# watch.net
KiCad netlist of a schematic drawn in EAGLE
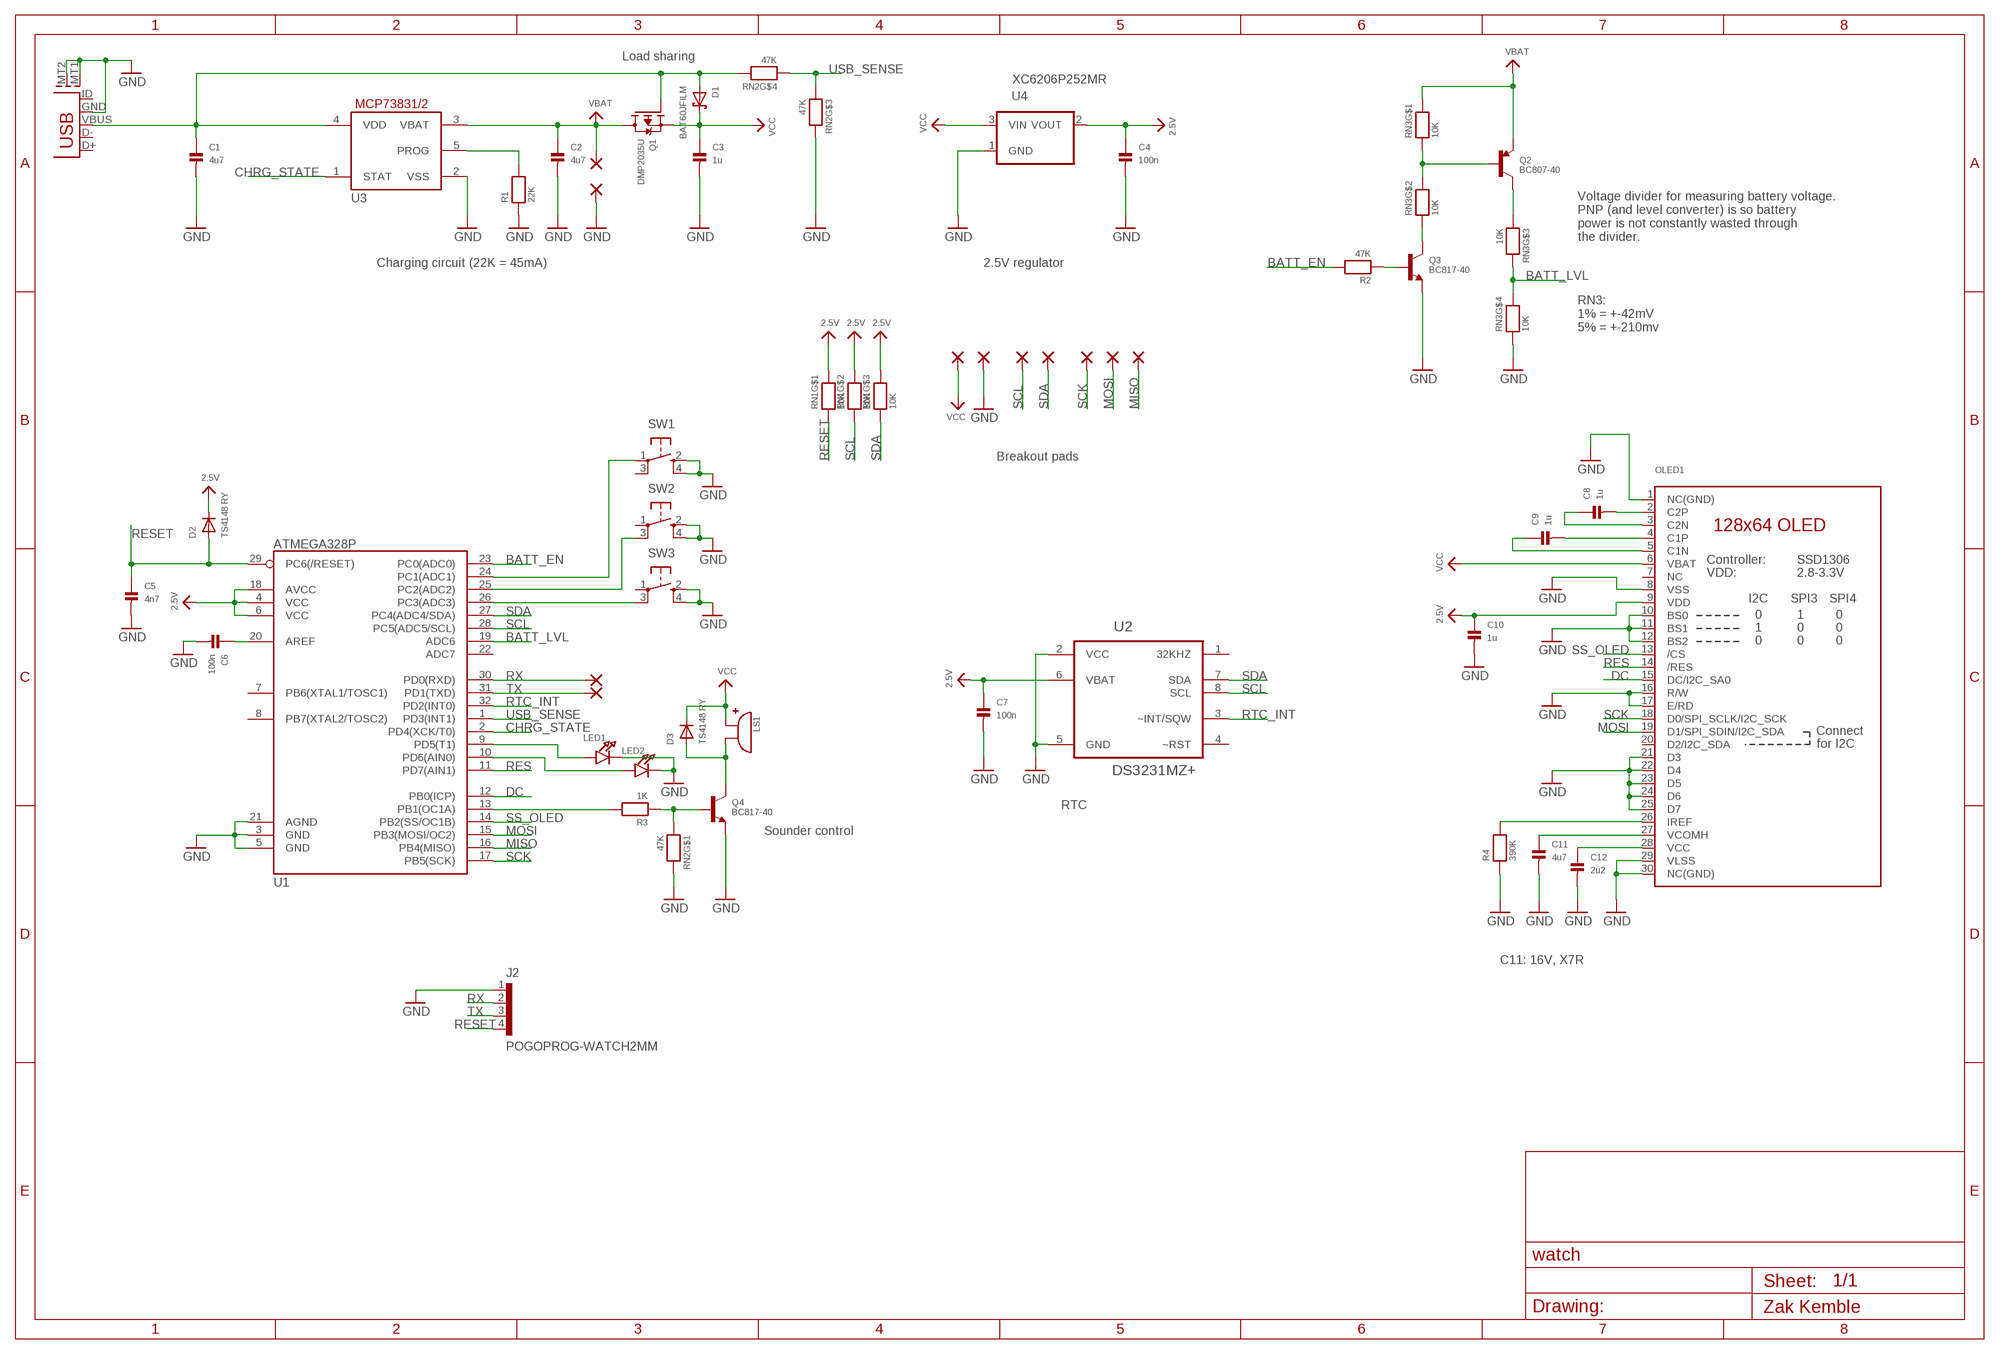
[diagram p0: schematic, sheet 1]

(export (version "E")
  (design (tool "Eeschema 10.0.6"))
  (components
    (comp (ref "C1")
      (value "4u7")
      (footprint "eagle-import:0805")
      (libsource (lib "eagle-import") (part "CAP_CERAMIC0805"))
    )
    (comp (ref "C2")
      (value "4u7")
      (footprint "eagle-import:0805")
      (libsource (lib "eagle-import") (part "CAP_CERAMIC0805"))
    )
    (comp (ref "C3")
      (value "1u")
      (footprint "eagle-import:0805")
      (libsource (lib "eagle-import") (part "CAP_CERAMIC0805"))
    )
    (comp (ref "C4")
      (value "100n")
      (footprint "eagle-import:0805")
      (libsource (lib "eagle-import") (part "CAP_CERAMIC0805"))
    )
    (comp (ref "C5")
      (value "4n7")
      (footprint "eagle-import:0805")
      (libsource (lib "eagle-import") (part "CAP_CERAMIC0805"))
    )
    (comp (ref "C6")
      (value "100n")
      (footprint "eagle-import:0805")
      (libsource (lib "eagle-import") (part "CAP_CERAMIC0805"))
    )
    (comp (ref "C7")
      (value "100n")
      (footprint "eagle-import:0805")
      (libsource (lib "eagle-import") (part "CAP_CERAMIC0805"))
    )
    (comp (ref "C8")
      (value "1u")
      (footprint "eagle-import:0805")
      (libsource (lib "eagle-import") (part "CAP_CERAMIC0805"))
    )
    (comp (ref "C9")
      (value "1u")
      (footprint "eagle-import:0805")
      (libsource (lib "eagle-import") (part "CAP_CERAMIC0805"))
    )
    (comp (ref "C10")
      (value "1u")
      (footprint "eagle-import:0805")
      (libsource (lib "eagle-import") (part "CAP_CERAMIC0805"))
    )
    (comp (ref "C11")
      (value "4u7")
      (footprint "eagle-import:0805")
      (libsource (lib "eagle-import") (part "CAP_CERAMIC0805"))
    )
    (comp (ref "C12")
      (value "2u2")
      (footprint "eagle-import:0805")
      (libsource (lib "eagle-import") (part "CAP_CERAMIC0805"))
    )
    (comp (ref "D1")
      (value "BAT60JFILM")
      (footprint "eagle-import:SOD-323")
      (libsource (lib "eagle-import") (part "DIODE-SCHOTTKYSOD-323"))
    )
    (comp (ref "D2")
      (value "TS4148 RY")
      (footprint "eagle-import:0805_DIODE")
      (libsource (lib "eagle-import") (part "DIODE_08050805"))
    )
    (comp (ref "D3")
      (value "TS4148 RY")
      (footprint "eagle-import:0805_DIODE")
      (libsource (lib "eagle-import") (part "DIODE_08050805"))
    )
    (comp (ref "J2")
      (value "POGOPROG-WATCH2MM")
      (footprint "eagle-import:POGOPROG_WATCH_2MM")
      (libsource (lib "eagle-import") (part "POGOPROG-WATCH2MM"))
    )
    (comp (ref "LED1")
      (value "LED0805")
      (footprint "eagle-import:CHIPLED_0805")
      (libsource (lib "eagle-import") (part "LED0805"))
    )
    (comp (ref "LED2")
      (value "LED0805")
      (footprint "eagle-import:CHIPLED_0805")
      (libsource (lib "eagle-import") (part "LED0805"))
    )
    (comp (ref "LS1")
      (value "ABMT-801-RC")
      (footprint "eagle-import:PIEZO")
      (libsource (lib "eagle-import") (part "ABMT-801-RC"))
    )
    (comp (ref "OLED1")
      (value "DISP_OLED_UG-2864HSWEG01_NOOUTLINEWATCH")
      (footprint "eagle-import:UG-2864HSWEG01_1.3_WRAPAROUND_WATCH")
      (libsource (lib "eagle-import") (part "DISP_OLED_UG-2864HSWEG01_NOOUTLINEWATCH"))
    )
    (comp (ref "PAD1")
      (value "SMD2")
      (footprint "eagle-import:SMD1,27-2,54")
      (libsource (lib "eagle-import") (part "SMD2"))
    )
    (comp (ref "PAD2")
      (value "SMD2")
      (footprint "eagle-import:SMD1,27-2,54")
      (libsource (lib "eagle-import") (part "SMD2"))
    )
    (comp (ref "PAD3")
      (value "SMD2")
      (footprint "eagle-import:SMD1,27-2,54")
      (libsource (lib "eagle-import") (part "SMD2"))
    )
    (comp (ref "PAD4")
      (value "SMD2")
      (footprint "eagle-import:SMD1,27-2,54")
      (libsource (lib "eagle-import") (part "SMD2"))
    )
    (comp (ref "PAD5")
      (value "SMD2")
      (footprint "eagle-import:SMD1,27-2,54")
      (libsource (lib "eagle-import") (part "SMD2"))
    )
    (comp (ref "PAD6")
      (value "SMD2")
      (footprint "eagle-import:SMD1,27-2,54")
      (libsource (lib "eagle-import") (part "SMD2"))
    )
    (comp (ref "PAD7")
      (value "SMD2")
      (footprint "eagle-import:SMD1,27-2,54")
      (libsource (lib "eagle-import") (part "SMD2"))
    )
    (comp (ref "PAD8")
      (value "SMD2")
      (footprint "eagle-import:SMD1,27-2,54")
      (libsource (lib "eagle-import") (part "SMD2"))
    )
    (comp (ref "PAD10")
      (value "SMD2")
      (footprint "eagle-import:SMD1,27-2,54")
      (libsource (lib "eagle-import") (part "SMD2"))
    )
    (comp (ref "PAD11")
      (value "SMD2")
      (footprint "eagle-import:SMD1,27-2,54")
      (libsource (lib "eagle-import") (part "SMD2"))
    )
    (comp (ref "PAD12")
      (value "SMD2")
      (footprint "eagle-import:SMD1,27-2,54")
      (libsource (lib "eagle-import") (part "SMD2"))
    )
    (comp (ref "Q1")
      (value "DMP2035U")
      (footprint "eagle-import:SOT23-WIDE")
      (libsource (lib "eagle-import") (part "MOSFET-PWIDE"))
    )
    (comp (ref "Q2")
      (value "BC807-40")
      (footprint "eagle-import:SOT23-WIDE")
      (libsource (lib "eagle-import") (part "TRANSISTOR_PNPWIDE"))
    )
    (comp (ref "Q3")
      (value "BC817-40")
      (footprint "eagle-import:SOT23-WIDE")
      (libsource (lib "eagle-import") (part "TRANSISTOR_NPNWIDE"))
    )
    (comp (ref "Q4")
      (value "BC817-40")
      (footprint "eagle-import:SOT23-WIDE")
      (libsource (lib "eagle-import") (part "TRANSISTOR_NPNWIDE"))
    )
    (comp (ref "R1")
      (value "22K")
      (footprint "eagle-import:0805")
      (libsource (lib "eagle-import") (part "RESISTOR0805"))
    )
    (comp (ref "R2")
      (value "47K")
      (footprint "eagle-import:0805")
      (libsource (lib "eagle-import") (part "RESISTOR0805"))
    )
    (comp (ref "R3")
      (value "1K")
      (footprint "eagle-import:0805")
      (libsource (lib "eagle-import") (part "RESISTOR0805"))
    )
    (comp (ref "R4")
      (value "390K")
      (footprint "eagle-import:0805")
      (libsource (lib "eagle-import") (part "RESISTOR0805"))
    )
    (comp (ref "RN1")
      (value "10K")
      (footprint "eagle-import:RESPACK_4X0603")
      (libsource (lib "eagle-import") (part "RESISTOR_4PACK"))
    )
    (comp (ref "RN2")
      (value "47K")
      (footprint "eagle-import:RESPACK_4X0603")
      (libsource (lib "eagle-import") (part "RESISTOR_4PACK"))
    )
    (comp (ref "RN3")
      (value "10K")
      (footprint "eagle-import:RESPACK_4X0603")
      (libsource (lib "eagle-import") (part "RESISTOR_4PACK"))
    )
    (comp (ref "SW1")
      (value "SPST_TACTRA")
      (footprint "eagle-import:TACT_SMD2")
      (libsource (lib "eagle-import") (part "SPST_TACTRA"))
    )
    (comp (ref "SW2")
      (value "SPST_TACTRA")
      (footprint "eagle-import:TACT_SMD2")
      (libsource (lib "eagle-import") (part "SPST_TACTRA"))
    )
    (comp (ref "SW3")
      (value "SPST_TACTRA")
      (footprint "eagle-import:TACT_SMD2")
      (libsource (lib "eagle-import") (part "SPST_TACTRA"))
    )
    (comp (ref "U1")
      (value "ATMEGA328P")
      (footprint "eagle-import:TQFP32-08")
      (libsource (lib "eagle-import") (part "ATMEGA328_SMT"))
    )
    (comp (ref "U2")
      (value "DS3231MZ+")
      (footprint "eagle-import:SOIC8_150MIL_SMPAD")
      (libsource (lib "eagle-import") (part "DS3231MZ+SMPAD"))
    )
    (comp (ref "U3")
      (value "MCP73832T-2ACI/OT")
      (footprint "eagle-import:SOT23-5L")
      (libsource (lib "eagle-import") (part "MCP73831/OT"))
    )
    (comp (ref "U4")
      (value "XC6206P252MR")
      (footprint "eagle-import:SOT-23")
      (libsource (lib "eagle-import") (part "MCP1700T-2502E/TTWIDE_PAD"))
    )
    (comp (ref "USB1")
      (value "USB-MICROBLARGEPAD")
      (footprint "eagle-import:USB-MICROB_LARGEPAD")
      (libsource (lib "eagle-import") (part "USB-MICROBLARGEPAD"))
    )
  )
  (nets
    (net (code "1") (name "/BATT_EN") (class "Default")
      (node (ref "R2") (pin "2") (pinfunction "2_2") (pintype "passive"))
      (node (ref "U1") (pin "23") (pinfunction "PC0(ADC0)_23") (pintype "bidirectional"))
    )
    (net (code "2") (name "/BATT_LVL") (class "Default")
      (node (ref "RN3") (pin "5") (pinfunction "2_5") (pintype "passive"))
      (node (ref "RN3") (pin "6") (pinfunction "2_6") (pintype "passive"))
      (node (ref "U1") (pin "19") (pinfunction "ADC6_19") (pintype "bidirectional"))
    )
    (net (code "3") (name "/CHRG_STATE") (class "Default")
      (node (ref "U1") (pin "2") (pinfunction "PD4(XCK/T0)_2") (pintype "bidirectional"))
      (node (ref "U3") (pin "1") (pinfunction "STAT_1") (pintype "output"))
    )
    (net (code "4") (name "/DC") (class "Default")
      (node (ref "OLED1") (pin "15") (pinfunction "DC/I2C_SA0_15") (pintype "input"))
      (node (ref "U1") (pin "12") (pinfunction "PB0(ICP)_12") (pintype "bidirectional"))
    )
    (net (code "5") (name "/MISO") (class "Default")
      (node (ref "PAD12") (pin "1") (pinfunction "P_1") (pintype "passive"))
      (node (ref "U1") (pin "16") (pinfunction "PB4(MISO)_16") (pintype "bidirectional"))
    )
    (net (code "6") (name "/MOSI") (class "Default")
      (node (ref "OLED1") (pin "19") (pinfunction "D1/SPI_SDIN/I2C_SDA_19") (pintype "bidirectional"))
      (node (ref "PAD11") (pin "1") (pinfunction "P_1") (pintype "passive"))
      (node (ref "U1") (pin "15") (pinfunction "PB3(MOSI/OC2)_15") (pintype "bidirectional"))
    )
    (net (code "7") (name "/RES") (class "Default")
      (node (ref "OLED1") (pin "14") (pinfunction "/RES_14") (pintype "input"))
      (node (ref "U1") (pin "11") (pinfunction "PD7(AIN1)_11") (pintype "bidirectional"))
    )
    (net (code "8") (name "/RESET") (class "Default")
      (node (ref "C5") (pin "1") (pinfunction "P$1_1") (pintype "passive"))
      (node (ref "D2") (pin "1") (pinfunction "A_1") (pintype "passive"))
      (node (ref "J2") (pin "4") (pinfunction "4_4") (pintype "bidirectional"))
      (node (ref "RN1") (pin "1") (pinfunction "1_1") (pintype "passive"))
      (node (ref "U1") (pin "29") (pinfunction "PC6(/RESET)_29") (pintype "bidirectional"))
    )
    (net (code "9") (name "/RTC_INT") (class "Default")
      (node (ref "U1") (pin "32") (pinfunction "PD2(INT0)_32") (pintype "bidirectional"))
      (node (ref "U2") (pin "3") (pinfunction "~{INT/SQW}_3") (pintype "output"))
    )
    (net (code "10") (name "/RX") (class "Default")
      (node (ref "J2") (pin "2") (pinfunction "2_2") (pintype "bidirectional"))
      (node (ref "PAD3") (pin "1") (pinfunction "P_1") (pintype "passive"))
      (node (ref "U1") (pin "30") (pinfunction "PD0(RXD)_30") (pintype "bidirectional"))
    )
    (net (code "11") (name "/SCK") (class "Default")
      (node (ref "OLED1") (pin "18") (pinfunction "D0/SPI_SCLK/I2C_SCK_18") (pintype "bidirectional"))
      (node (ref "PAD10") (pin "1") (pinfunction "P_1") (pintype "passive"))
      (node (ref "U1") (pin "17") (pinfunction "PB5(SCK)_17") (pintype "bidirectional"))
    )
    (net (code "12") (name "/SCL") (class "Default")
      (node (ref "PAD8") (pin "1") (pinfunction "P_1") (pintype "passive"))
      (node (ref "RN1") (pin "2") (pinfunction "1_2") (pintype "passive"))
      (node (ref "U1") (pin "28") (pinfunction "PC5(ADC5/SCL)_28") (pintype "bidirectional"))
      (node (ref "U2") (pin "8") (pinfunction "SCL_8") (pintype "input"))
    )
    (net (code "13") (name "/SDA") (class "Default")
      (node (ref "PAD7") (pin "1") (pinfunction "P_1") (pintype "passive"))
      (node (ref "RN1") (pin "3") (pinfunction "1_3") (pintype "passive"))
      (node (ref "U1") (pin "27") (pinfunction "PC4(ADC4/SDA)_27") (pintype "bidirectional"))
      (node (ref "U2") (pin "7") (pinfunction "SDA_7") (pintype "bidirectional"))
    )
    (net (code "14") (name "/SS_OLED") (class "Default")
      (node (ref "OLED1") (pin "13") (pinfunction "/CS_13") (pintype "input"))
      (node (ref "U1") (pin "14") (pinfunction "PB2(SS/OC1B)_14") (pintype "bidirectional"))
    )
    (net (code "15") (name "/TX") (class "Default")
      (node (ref "J2") (pin "3") (pinfunction "3_3") (pintype "bidirectional"))
      (node (ref "PAD4") (pin "1") (pinfunction "P_1") (pintype "passive"))
      (node (ref "U1") (pin "31") (pinfunction "PD1(TXD)_31") (pintype "bidirectional"))
    )
    (net (code "16") (name "/USB_SENSE") (class "Default")
      (node (ref "RN2") (pin "3") (pinfunction "1_3") (pintype "passive"))
      (node (ref "RN2") (pin "4") (pinfunction "1_4") (pintype "passive"))
      (node (ref "U1") (pin "1") (pinfunction "PD3(INT1)_1") (pintype "bidirectional"))
    )
    (net (code "17") (name "2.5V") (class "Default")
      (node (ref "C10") (pin "1") (pinfunction "P$1_1") (pintype "passive"))
      (node (ref "C4") (pin "1") (pinfunction "P$1_1") (pintype "passive"))
      (node (ref "C7") (pin "1") (pinfunction "P$1_1") (pintype "passive"))
      (node (ref "D2") (pin "2") (pinfunction "C_2") (pintype "passive"))
      (node (ref "OLED1") (pin "9") (pinfunction "VDD_9") (pintype "power_in"))
      (node (ref "RN1") (pin "6") (pinfunction "2_6") (pintype "passive"))
      (node (ref "RN1") (pin "7") (pinfunction "2_7") (pintype "passive"))
      (node (ref "RN1") (pin "8") (pinfunction "2_8") (pintype "passive"))
      (node (ref "U1") (pin "18") (pinfunction "AVCC_18") (pintype "bidirectional"))
      (node (ref "U1") (pin "4") (pinfunction "VCC_4") (pintype "bidirectional"))
      (node (ref "U1") (pin "6") (pinfunction "VCC_6") (pintype "bidirectional"))
      (node (ref "U2") (pin "6") (pinfunction "VBAT_6") (pintype "power_in"))
      (node (ref "U4") (pin "2") (pinfunction "VOUT_2") (pintype "output"))
    )
    (net (code "18") (name "GND") (class "Default")
      (node (ref "C1") (pin "2") (pinfunction "P$2_2") (pintype "passive"))
      (node (ref "C10") (pin "2") (pinfunction "P$2_2") (pintype "passive"))
      (node (ref "C11") (pin "2") (pinfunction "P$2_2") (pintype "passive"))
      (node (ref "C12") (pin "2") (pinfunction "P$2_2") (pintype "passive"))
      (node (ref "C2") (pin "2") (pinfunction "P$2_2") (pintype "passive"))
      (node (ref "C3") (pin "2") (pinfunction "P$2_2") (pintype "passive"))
      (node (ref "C4") (pin "2") (pinfunction "P$2_2") (pintype "passive"))
      (node (ref "C5") (pin "2") (pinfunction "P$2_2") (pintype "passive"))
      (node (ref "C6") (pin "2") (pinfunction "P$2_2") (pintype "passive"))
      (node (ref "C7") (pin "2") (pinfunction "P$2_2") (pintype "passive"))
      (node (ref "J2") (pin "1") (pinfunction "1_1") (pintype "bidirectional"))
      (node (ref "LED1") (pin "C") (pinfunction "C_C") (pintype "passive"))
      (node (ref "LED2") (pin "C") (pinfunction "C_C") (pintype "passive"))
      (node (ref "OLED1") (pin "1") (pinfunction "NC(GND)_1") (pintype "input"))
      (node (ref "OLED1") (pin "10") (pinfunction "BS0_10") (pintype "input"))
      (node (ref "OLED1") (pin "11") (pinfunction "BS1_11") (pintype "input"))
      (node (ref "OLED1") (pin "12") (pinfunction "BS2_12") (pintype "input"))
      (node (ref "OLED1") (pin "16") (pinfunction "R/W_16") (pintype "input"))
      (node (ref "OLED1") (pin "17") (pinfunction "E/RD_17") (pintype "input"))
      (node (ref "OLED1") (pin "21") (pinfunction "D3_21") (pintype "bidirectional"))
      (node (ref "OLED1") (pin "22") (pinfunction "D4_22") (pintype "bidirectional"))
      (node (ref "OLED1") (pin "23") (pinfunction "D5_23") (pintype "bidirectional"))
      (node (ref "OLED1") (pin "24") (pinfunction "D6_24") (pintype "bidirectional"))
      (node (ref "OLED1") (pin "25") (pinfunction "D7_25") (pintype "bidirectional"))
      (node (ref "OLED1") (pin "29") (pinfunction "VLSS_29") (pintype "power_in"))
      (node (ref "OLED1") (pin "30") (pinfunction "NC(GND)_30") (pintype "input"))
      (node (ref "OLED1") (pin "8") (pinfunction "VSS_8") (pintype "power_in"))
      (node (ref "PAD2") (pin "1") (pinfunction "P_1") (pintype "passive"))
      (node (ref "PAD5") (pin "1") (pinfunction "P_1") (pintype "passive"))
      (node (ref "Q3") (pin "2") (pinfunction "E_2") (pintype "passive"))
      (node (ref "Q4") (pin "2") (pinfunction "E_2") (pintype "passive"))
      (node (ref "R1") (pin "1") (pinfunction "1_1") (pintype "passive"))
      (node (ref "R4") (pin "1") (pinfunction "1_1") (pintype "passive"))
      (node (ref "RN2") (pin "6") (pinfunction "2_6") (pintype "passive"))
      (node (ref "RN2") (pin "8") (pinfunction "2_8") (pintype "passive"))
      (node (ref "RN3") (pin "4") (pinfunction "1_4") (pintype "passive"))
      (node (ref "SW1") (pin "2") (pinfunction "S_2") (pintype "passive"))
      (node (ref "SW1") (pin "4") (pinfunction "S1_4") (pintype "passive"))
      (node (ref "SW2") (pin "2") (pinfunction "S_2") (pintype "passive"))
      (node (ref "SW2") (pin "4") (pinfunction "S1_4") (pintype "passive"))
      (node (ref "SW3") (pin "2") (pinfunction "S_2") (pintype "passive"))
      (node (ref "SW3") (pin "4") (pinfunction "S1_4") (pintype "passive"))
      (node (ref "U1") (pin "21") (pinfunction "AGND_21") (pintype "bidirectional"))
      (node (ref "U1") (pin "3") (pinfunction "GND_3") (pintype "bidirectional"))
      (node (ref "U1") (pin "5") (pinfunction "GND_5") (pintype "bidirectional"))
      (node (ref "U2") (pin "2") (pinfunction "VCC_2") (pintype "power_in"))
      (node (ref "U2") (pin "5") (pinfunction "GND_5") (pintype "passive"))
      (node (ref "U3") (pin "2") (pinfunction "VSS_2") (pintype "power_in"))
      (node (ref "U4") (pin "1") (pinfunction "GND_1") (pintype "passive"))
      (node (ref "USB1") (pin "GND") (pinfunction "GND_GND") (pintype "bidirectional"))
      (node (ref "USB1") (pin "MT1") (pinfunction "SHEILD1_MT1") (pintype "bidirectional"))
      (node (ref "USB1") (pin "MT2") (pinfunction "SHEILD2_MT2") (pintype "bidirectional"))
    )
    (net (code "19") (name "Net-(C1-P$1)") (class "Default")
      (node (ref "C1") (pin "1") (pinfunction "P$1_1") (pintype "passive"))
      (node (ref "D1") (pin "A") (pinfunction "A_A") (pintype "passive"))
      (node (ref "Q1") (pin "1") (pinfunction "G_1") (pintype "passive"))
      (node (ref "RN2") (pin "5") (pinfunction "2_5") (pintype "passive"))
      (node (ref "U3") (pin "4") (pinfunction "VDD_4") (pintype "power_in"))
      (node (ref "USB1") (pin "VBUS") (pinfunction "VBUS_VBUS") (pintype "bidirectional"))
    )
    (net (code "20") (name "Net-(C6-P$1)") (class "Default")
      (node (ref "C6") (pin "1") (pinfunction "P$1_1") (pintype "passive"))
      (node (ref "U1") (pin "20") (pinfunction "AREF_20") (pintype "bidirectional"))
    )
    (net (code "21") (name "Net-(C8-P$1)") (class "Default")
      (node (ref "C8") (pin "1") (pinfunction "P$1_1") (pintype "passive"))
      (node (ref "OLED1") (pin "3") (pinfunction "C2N_3") (pintype "input"))
    )
    (net (code "22") (name "Net-(C8-P$2)") (class "Default")
      (node (ref "C8") (pin "2") (pinfunction "P$2_2") (pintype "passive"))
      (node (ref "OLED1") (pin "2") (pinfunction "C2P_2") (pintype "input"))
    )
    (net (code "23") (name "Net-(C9-P$1)") (class "Default")
      (node (ref "C9") (pin "1") (pinfunction "P$1_1") (pintype "passive"))
      (node (ref "OLED1") (pin "5") (pinfunction "C1N_5") (pintype "input"))
    )
    (net (code "24") (name "Net-(C9-P$2)") (class "Default")
      (node (ref "C9") (pin "2") (pinfunction "P$2_2") (pintype "passive"))
      (node (ref "OLED1") (pin "4") (pinfunction "C1P_4") (pintype "input"))
    )
    (net (code "25") (name "Net-(C11-P$1)") (class "Default")
      (node (ref "C11") (pin "1") (pinfunction "P$1_1") (pintype "passive"))
      (node (ref "OLED1") (pin "27") (pinfunction "VCOMH_27") (pintype "output"))
    )
    (net (code "26") (name "Net-(C12-P$1)") (class "Default")
      (node (ref "C12") (pin "1") (pinfunction "P$1_1") (pintype "passive"))
      (node (ref "OLED1") (pin "28") (pinfunction "VCC_28") (pintype "power_in"))
    )
    (net (code "27") (name "Net-(D3-A)") (class "Default")
      (node (ref "D3") (pin "1") (pinfunction "A_1") (pintype "passive"))
      (node (ref "LS1") (pin "2") (pinfunction "GND_2") (pintype "passive"))
      (node (ref "Q4") (pin "3") (pinfunction "C_3") (pintype "passive"))
    )
    (net (code "28") (name "Net-(OLED1-IREF)") (class "Default")
      (node (ref "OLED1") (pin "26") (pinfunction "IREF_26") (pintype "input"))
      (node (ref "R4") (pin "2") (pinfunction "2_2") (pintype "passive"))
    )
    (net (code "29") (name "Net-(Q2-B)") (class "Default")
      (node (ref "Q2") (pin "1") (pinfunction "B_1") (pintype "passive"))
      (node (ref "RN3") (pin "1") (pinfunction "1_1") (pintype "passive"))
      (node (ref "RN3") (pin "7") (pinfunction "2_7") (pintype "passive"))
    )
    (net (code "30") (name "Net-(Q2-C)") (class "Default")
      (node (ref "Q2") (pin "3") (pinfunction "C_3") (pintype "passive"))
      (node (ref "RN3") (pin "3") (pinfunction "1_3") (pintype "passive"))
    )
    (net (code "31") (name "Net-(Q3-B)") (class "Default")
      (node (ref "Q3") (pin "1") (pinfunction "B_1") (pintype "passive"))
      (node (ref "R2") (pin "1") (pinfunction "1_1") (pintype "passive"))
    )
    (net (code "32") (name "Net-(Q3-C)") (class "Default")
      (node (ref "Q3") (pin "3") (pinfunction "C_3") (pintype "passive"))
      (node (ref "RN3") (pin "2") (pinfunction "1_2") (pintype "passive"))
    )
    (net (code "33") (name "Net-(Q4-B)") (class "Default")
      (node (ref "Q4") (pin "1") (pinfunction "B_1") (pintype "passive"))
      (node (ref "R3") (pin "1") (pinfunction "1_1") (pintype "passive"))
      (node (ref "RN2") (pin "1") (pinfunction "1_1") (pintype "passive"))
    )
    (net (code "34") (name "Net-(SW1-P)") (class "Default")
      (node (ref "SW1") (pin "1") (pinfunction "P_1") (pintype "passive"))
      (node (ref "U1") (pin "24") (pinfunction "PC1(ADC1)_24") (pintype "bidirectional"))
    )
    (net (code "35") (name "Net-(SW2-P1)") (class "Default")
      (node (ref "SW2") (pin "3") (pinfunction "P1_3") (pintype "passive"))
      (node (ref "U1") (pin "25") (pinfunction "PC2(ADC2)_25") (pintype "bidirectional"))
    )
    (net (code "36") (name "Net-(SW3-P1)") (class "Default")
      (node (ref "SW3") (pin "3") (pinfunction "P1_3") (pintype "passive"))
      (node (ref "U1") (pin "26") (pinfunction "PC3(ADC3)_26") (pintype "bidirectional"))
    )
    (net (code "37") (name "Net-(U1-PB1(OC1A))") (class "Default")
      (node (ref "R3") (pin "2") (pinfunction "2_2") (pintype "passive"))
      (node (ref "U1") (pin "13") (pinfunction "PB1(OC1A)_13") (pintype "bidirectional"))
    )
    (net (code "38") (name "Net-(U1-PD5(T1))") (class "Default")
      (node (ref "LED1") (pin "A") (pinfunction "A_A") (pintype "passive"))
      (node (ref "U1") (pin "9") (pinfunction "PD5(T1)_9") (pintype "bidirectional"))
    )
    (net (code "39") (name "Net-(U1-PD6(AIN0))") (class "Default")
      (node (ref "LED2") (pin "A") (pinfunction "A_A") (pintype "passive"))
      (node (ref "U1") (pin "10") (pinfunction "PD6(AIN0)_10") (pintype "bidirectional"))
    )
    (net (code "40") (name "Net-(U3-PROG)") (class "Default")
      (node (ref "R1") (pin "2") (pinfunction "2_2") (pintype "passive"))
      (node (ref "U3") (pin "5") (pinfunction "PROG_5") (pintype "input"))
    )
    (net (code "41") (name "VBAT") (class "Default")
      (node (ref "C2") (pin "1") (pinfunction "P$1_1") (pintype "passive"))
      (node (ref "PAD1") (pin "1") (pinfunction "P_1") (pintype "passive"))
      (node (ref "Q1") (pin "3") (pinfunction "D_3") (pintype "passive"))
      (node (ref "Q2") (pin "2") (pinfunction "E_2") (pintype "passive"))
      (node (ref "RN3") (pin "8") (pinfunction "2_8") (pintype "passive"))
      (node (ref "U3") (pin "3") (pinfunction "VBAT_3") (pintype "bidirectional"))
    )
    (net (code "42") (name "VCC") (class "Default")
      (node (ref "C3") (pin "1") (pinfunction "P$1_1") (pintype "passive"))
      (node (ref "D1") (pin "C") (pinfunction "C_C") (pintype "passive"))
      (node (ref "D3") (pin "2") (pinfunction "C_2") (pintype "passive"))
      (node (ref "LS1") (pin "1") (pinfunction "VCC_1") (pintype "passive"))
      (node (ref "OLED1") (pin "6") (pinfunction "VBAT_6") (pintype "input"))
      (node (ref "PAD6") (pin "1") (pinfunction "P_1") (pintype "passive"))
      (node (ref "Q1") (pin "2") (pinfunction "S_2") (pintype "passive"))
      (node (ref "U4") (pin "3") (pinfunction "VIN_3") (pintype "power_in"))
    )
    (net (code "43") (name "unconnected-(OLED1-D2{slash}I2C_SDA-Pad20)") (class "Default")
      (node (ref "OLED1") (pin "20") (pinfunction "D2/I2C_SDA_20") (pintype "bidirectional"))
    )
    (net (code "44") (name "unconnected-(OLED1-NC-Pad7)") (class "Default")
      (node (ref "OLED1") (pin "7") (pinfunction "NC_7") (pintype "no_connect"))
    )
    (net (code "45") (name "unconnected-(SW1-P1-Pad3)") (class "Default")
      (node (ref "SW1") (pin "3") (pinfunction "P1_3") (pintype "passive"))
    )
    (net (code "46") (name "unconnected-(SW2-P-Pad1)") (class "Default")
      (node (ref "SW2") (pin "1") (pinfunction "P_1") (pintype "passive"))
    )
    (net (code "47") (name "unconnected-(SW3-P-Pad1)") (class "Default")
      (node (ref "SW3") (pin "1") (pinfunction "P_1") (pintype "passive"))
    )
    (net (code "48") (name "unconnected-(U1-ADC7-Pad22)") (class "Default")
      (node (ref "U1") (pin "22") (pinfunction "ADC7_22") (pintype "bidirectional"))
    )
    (net (code "49") (name "unconnected-(U1-PB6(XTAL1{slash}TOSC1)-Pad7)") (class "Default")
      (node (ref "U1") (pin "7") (pinfunction "PB6(XTAL1/TOSC1)_7") (pintype "bidirectional"))
    )
    (net (code "50") (name "unconnected-(U1-PB7(XTAL2{slash}TOSC2)-Pad8)") (class "Default")
      (node (ref "U1") (pin "8") (pinfunction "PB7(XTAL2/TOSC2)_8") (pintype "bidirectional"))
    )
    (net (code "51") (name "unconnected-(U2-32KHZ-Pad1)") (class "Default")
      (node (ref "U2") (pin "1") (pinfunction "32KHZ_1") (pintype "output"))
    )
    (net (code "52") (name "unconnected-(U2-~{RST}-Pad4)") (class "Default")
      (node (ref "U2") (pin "4") (pinfunction "~{RST}_4") (pintype "bidirectional"))
    )
    (net (code "53") (name "unconnected-(USB1-PadD+)") (class "Default")
      (node (ref "USB1") (pin "D+") (pinfunction "D+_D+") (pintype "bidirectional"))
    )
    (net (code "54") (name "unconnected-(USB1-PadD-)") (class "Default")
      (node (ref "USB1") (pin "D-") (pinfunction "D-_D-") (pintype "bidirectional"))
    )
    (net (code "55") (name "unconnected-(USB1-PadID)") (class "Default")
      (node (ref "USB1") (pin "ID") (pinfunction "ID_ID") (pintype "bidirectional"))
    )
  )
)
